# Motor_Driver.net
KiCad netlist of a schematic drawn in Altium Designer
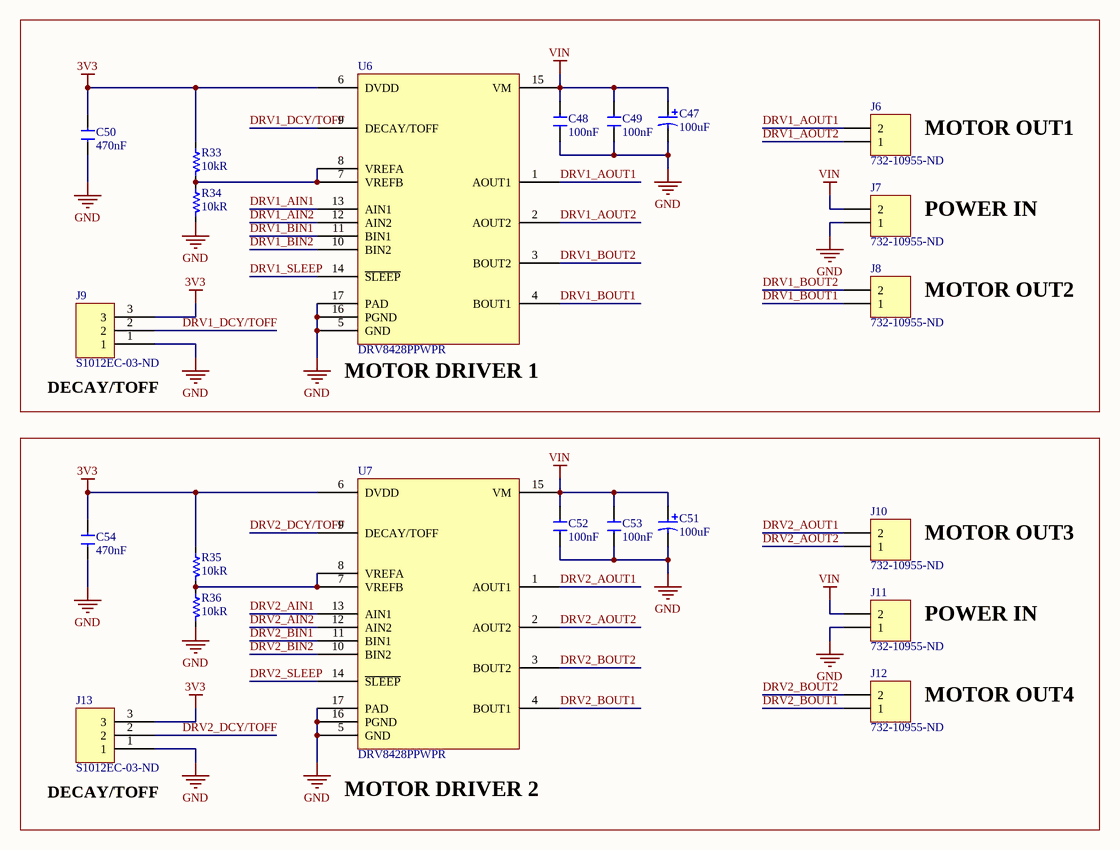
[diagram p0: Motor Driver.SchDoc]

(export (version "E")
  (design (tool "Eeschema 10.0.6"))
  (components
    (comp (ref "C47")
      (value "CAP_100uF_%20_25V_ALUM_SMD")
      (footprint "RADIAL-2_6.3MMX7.7MM")
      (description "CAP.EL.100uF 25V 6.3x7.7 105C 5000HRS SMD")
      (fields
        (field (name "TOLERANCE") "20%")
        (field (name "MANUFACTURER") "SAMYOUNG")
        (field (name "CAPACITANCE") "100uF")
      )
      (libsource (lib "Main Schematic Library") (part "CAP_100uF_%20_25V_ALUM_SMD"))
    )
    (comp (ref "C48")
      (value "CAP_0.1uF_50V_0805_X7R_CER")
      (footprint "0805_CAP")
      (description "Cap Ceramic 0.1uF 50V X7R 20% SMD 0805 125C Paper T/R")
      (fields
        (field (name "MANUFACTURER") "KEMET")
        (field (name "MANUFACTURER PART NUMBER") "C0805C104M5RACTU")
        (field (name "CAPACITANCE") "100nF")
      )
      (libsource (lib "Main Component Library") (part "CAP_0.1uF_50V_0805_X7R_CER"))
    )
    (comp (ref "C49")
      (value "CAP_0.1uF_50V_0805_X7R_CER")
      (footprint "0805_CAP")
      (description "Cap Ceramic 0.1uF 50V X7R 20% SMD 0805 125C Paper T/R")
      (fields
        (field (name "MANUFACTURER") "KEMET")
        (field (name "MANUFACTURER PART NUMBER") "C0805C104M5RACTU")
        (field (name "CAPACITANCE") "100nF")
      )
      (libsource (lib "Main Component Library") (part "CAP_0.1uF_50V_0805_X7R_CER"))
    )
    (comp (ref "C50")
      (value "CAP_0.47uF_%10_0805_25V_X7R_CER")
      (footprint "0805_CAP")
      (description "Cap Ceramic 0.47uF 25V X7R 10% SMD 0805 125°C Embossed Plastic T/R")
      (fields
        (field (name "MANUFACTURER") "Samsung")
        (field (name "MANUFACTURER PART NUMBER") "CL21B474KAFNNNG")
        (field (name "CAPACITANCE") "470nF")
      )
      (libsource (lib "Main Component Library") (part "CAP_0.47uF_%10_0805_25V_X7R_CER"))
    )
    (comp (ref "C51")
      (value "CAP_100uF_%20_25V_ALUM_SMD")
      (footprint "RADIAL-2_6.3MMX7.7MM")
      (description "CAP.EL.100uF 25V 6.3x7.7 105C 5000HRS SMD")
      (fields
        (field (name "TOLERANCE") "20%")
        (field (name "MANUFACTURER") "SAMYOUNG")
        (field (name "CAPACITANCE") "100uF")
      )
      (libsource (lib "Main Schematic Library") (part "CAP_100uF_%20_25V_ALUM_SMD"))
    )
    (comp (ref "C52")
      (value "CAP_0.1uF_50V_0805_X7R_CER")
      (footprint "0805_CAP")
      (description "Cap Ceramic 0.1uF 50V X7R 20% SMD 0805 125C Paper T/R")
      (fields
        (field (name "MANUFACTURER") "KEMET")
        (field (name "MANUFACTURER PART NUMBER") "C0805C104M5RACTU")
        (field (name "CAPACITANCE") "100nF")
      )
      (libsource (lib "Main Component Library") (part "CAP_0.1uF_50V_0805_X7R_CER"))
    )
    (comp (ref "C53")
      (value "CAP_0.1uF_50V_0805_X7R_CER")
      (footprint "0805_CAP")
      (description "Cap Ceramic 0.1uF 50V X7R 20% SMD 0805 125C Paper T/R")
      (fields
        (field (name "MANUFACTURER") "KEMET")
        (field (name "MANUFACTURER PART NUMBER") "C0805C104M5RACTU")
        (field (name "CAPACITANCE") "100nF")
      )
      (libsource (lib "Main Component Library") (part "CAP_0.1uF_50V_0805_X7R_CER"))
    )
    (comp (ref "C54")
      (value "CAP_0.47uF_%10_0805_25V_X7R_CER")
      (footprint "0805_CAP")
      (description "Cap Ceramic 0.47uF 25V X7R 10% SMD 0805 125°C Embossed Plastic T/R")
      (fields
        (field (name "MANUFACTURER") "Samsung")
        (field (name "MANUFACTURER PART NUMBER") "CL21B474KAFNNNG")
        (field (name "CAPACITANCE") "470nF")
      )
      (libsource (lib "Main Component Library") (part "CAP_0.47uF_%10_0805_25V_X7R_CER"))
    )
    (comp (ref "J6")
      (value "CONN_1X2_Terminal Block")
      (footprint "1x2_TERMINAL BLOCK")
      (description "Series 1377 - 5.00 mm Horizontal Entry with Pressure Clamp WR-TBL, 2 pin")
      (fields
        (field (name "MANUFACTURER") "Wurth Electronics")
        (field (name "MANUFACTURER PART NUMBER") "691137710002")
        (field (name "SUPPLIER PART NUMBER 1") "732-10955-ND")
      )
      (libsource (lib "Main Component Library") (part "CONN_1X2_Terminal Block"))
    )
    (comp (ref "J7")
      (value "CONN_1X2_Terminal Block")
      (footprint "1x2_TERMINAL BLOCK")
      (description "Series 1377 - 5.00 mm Horizontal Entry with Pressure Clamp WR-TBL, 2 pin")
      (fields
        (field (name "MANUFACTURER") "Wurth Electronics")
        (field (name "MANUFACTURER PART NUMBER") "691137710002")
        (field (name "SUPPLIER PART NUMBER 1") "732-10955-ND")
      )
      (libsource (lib "Main Component Library") (part "CONN_1X2_Terminal Block"))
    )
    (comp (ref "J8")
      (value "CONN_1X2_Terminal Block")
      (footprint "1x2_TERMINAL BLOCK")
      (description "Series 1377 - 5.00 mm Horizontal Entry with Pressure Clamp WR-TBL, 2 pin")
      (fields
        (field (name "MANUFACTURER") "Wurth Electronics")
        (field (name "MANUFACTURER PART NUMBER") "691137710002")
        (field (name "SUPPLIER PART NUMBER 1") "732-10955-ND")
      )
      (libsource (lib "Main Component Library") (part "CONN_1X2_Terminal Block"))
    )
    (comp (ref "J9")
      (value "CONN_1X3_2.54mm_Male Header")
      (footprint "DIP_1X3_MALE_HEADER_2.54_PITCH")
      (description "Conn Header Vert 3POS 2.54MM")
      (fields
        (field (name "MANUFACTURER") "Sullins")
        (field (name "MANUFACTURER PART NUMBER") "PREC003SAAN-RC")
        (field (name "SUPPLIER PART NUMBER 1") "S1012EC-03-ND")
      )
      (libsource (lib "Main Schematic Library") (part "CONN_1X3_2.54mm_Male Header"))
    )
    (comp (ref "J10")
      (value "CONN_1X2_Terminal Block")
      (footprint "1x2_TERMINAL BLOCK")
      (description "Series 1377 - 5.00 mm Horizontal Entry with Pressure Clamp WR-TBL, 2 pin")
      (fields
        (field (name "MANUFACTURER") "Wurth Electronics")
        (field (name "MANUFACTURER PART NUMBER") "691137710002")
        (field (name "SUPPLIER PART NUMBER 1") "732-10955-ND")
      )
      (libsource (lib "Main Component Library") (part "CONN_1X2_Terminal Block"))
    )
    (comp (ref "J11")
      (value "CONN_1X2_Terminal Block")
      (footprint "1x2_TERMINAL BLOCK")
      (description "Series 1377 - 5.00 mm Horizontal Entry with Pressure Clamp WR-TBL, 2 pin")
      (fields
        (field (name "MANUFACTURER") "Wurth Electronics")
        (field (name "MANUFACTURER PART NUMBER") "691137710002")
        (field (name "SUPPLIER PART NUMBER 1") "732-10955-ND")
      )
      (libsource (lib "Main Component Library") (part "CONN_1X2_Terminal Block"))
    )
    (comp (ref "J12")
      (value "CONN_1X2_Terminal Block")
      (footprint "1x2_TERMINAL BLOCK")
      (description "Series 1377 - 5.00 mm Horizontal Entry with Pressure Clamp WR-TBL, 2 pin")
      (fields
        (field (name "MANUFACTURER") "Wurth Electronics")
        (field (name "MANUFACTURER PART NUMBER") "691137710002")
        (field (name "SUPPLIER PART NUMBER 1") "732-10955-ND")
      )
      (libsource (lib "Main Component Library") (part "CONN_1X2_Terminal Block"))
    )
    (comp (ref "J13")
      (value "CONN_1X3_2.54mm_Male Header")
      (footprint "DIP_1X3_MALE_HEADER_2.54_PITCH")
      (description "Conn Header Vert 3POS 2.54MM")
      (fields
        (field (name "MANUFACTURER") "Sullins")
        (field (name "MANUFACTURER PART NUMBER") "PREC003SAAN-RC")
        (field (name "SUPPLIER PART NUMBER 1") "S1012EC-03-ND")
      )
      (libsource (lib "Main Schematic Library") (part "CONN_1X3_2.54mm_Male Header"))
    )
    (comp (ref "R33")
      (value "10k Ohms")
      (footprint "0805_RES")
      (description "Res SMD 0805 10K 1% 0.125W T.C.100PPM")
      (fields
        (field (name "MANUFACTURER") "TDK")
        (field (name "MANUFACTURER PART NUMBER") "C2012X7R1H104K085AA")
        (field (name "RESISTANCE") "10kR")
      )
      (libsource (lib "Main Component Library") (part "RES_10K OHM_%1_0805_1/8W"))
    )
    (comp (ref "R34")
      (value "10k Ohms")
      (footprint "0805_RES")
      (description "Res SMD 0805 10K 1% 0.125W T.C.100PPM")
      (fields
        (field (name "MANUFACTURER") "TDK")
        (field (name "MANUFACTURER PART NUMBER") "C2012X7R1H104K085AA")
        (field (name "RESISTANCE") "10kR")
      )
      (libsource (lib "Main Component Library") (part "RES_10K OHM_%1_0805_1/8W"))
    )
    (comp (ref "R35")
      (value "10k Ohms")
      (footprint "0805_RES")
      (description "Res SMD 0805 10K 1% 0.125W T.C.100PPM")
      (fields
        (field (name "MANUFACTURER") "TDK")
        (field (name "MANUFACTURER PART NUMBER") "C2012X7R1H104K085AA")
        (field (name "RESISTANCE") "10kR")
      )
      (libsource (lib "Main Component Library") (part "RES_10K OHM_%1_0805_1/8W"))
    )
    (comp (ref "R36")
      (value "10k Ohms")
      (footprint "0805_RES")
      (description "Res SMD 0805 10K 1% 0.125W T.C.100PPM")
      (fields
        (field (name "MANUFACTURER") "TDK")
        (field (name "MANUFACTURER PART NUMBER") "C2012X7R1H104K085AA")
        (field (name "RESISTANCE") "10kR")
      )
      (libsource (lib "Main Component Library") (part "RES_10K OHM_%1_0805_1/8W"))
    )
    (comp (ref "U6")
      (value "DRV8428PPWPR")
      (footprint "TSOP65P640X120_HS-17N")
      (fields (field (name "MANUFACTURER") "Texas Instruments"))
      (libsource (lib "Main Schematic Library") (part "IC_MOTOR DRIVER_DRV8428PPWPR"))
    )
    (comp (ref "U7")
      (value "DRV8428PPWPR")
      (footprint "TSOP65P640X120_HS-17N")
      (fields (field (name "MANUFACTURER") "Texas Instruments"))
      (libsource (lib "Main Schematic Library") (part "IC_MOTOR DRIVER_DRV8428PPWPR"))
    )
  )
  (nets
    (net (code "1") (name "/DRV1_AIN1") (class "Default")
      (node (ref "U6") (pin "13") (pinfunction "AIN1_13") (pintype "passive"))
    )
    (net (code "2") (name "/DRV1_AIN2") (class "Default")
      (node (ref "U6") (pin "12") (pinfunction "AIN2_12") (pintype "passive"))
    )
    (net (code "3") (name "/DRV1_AOUT1") (class "Default")
      (node (ref "J6") (pin "2") (pinfunction "2_2") (pintype "passive"))
      (node (ref "U6") (pin "1") (pinfunction "AOUT1_1") (pintype "passive"))
    )
    (net (code "4") (name "/DRV1_AOUT2") (class "Default")
      (node (ref "J6") (pin "1") (pinfunction "1_1") (pintype "passive"))
      (node (ref "U6") (pin "2") (pinfunction "AOUT2_2") (pintype "passive"))
    )
    (net (code "5") (name "/DRV1_BIN1") (class "Default")
      (node (ref "U6") (pin "11") (pinfunction "BIN1_11") (pintype "passive"))
    )
    (net (code "6") (name "/DRV1_BIN2") (class "Default")
      (node (ref "U6") (pin "10") (pinfunction "BIN2_10") (pintype "passive"))
    )
    (net (code "7") (name "/DRV1_BOUT1") (class "Default")
      (node (ref "J8") (pin "1") (pinfunction "1_1") (pintype "passive"))
      (node (ref "U6") (pin "4") (pinfunction "BOUT1_4") (pintype "passive"))
    )
    (net (code "8") (name "/DRV1_BOUT2") (class "Default")
      (node (ref "J8") (pin "2") (pinfunction "2_2") (pintype "passive"))
      (node (ref "U6") (pin "3") (pinfunction "BOUT2_3") (pintype "passive"))
    )
    (net (code "9") (name "/DRV1_DCY{slash}TOFF") (class "Default")
      (node (ref "J9") (pin "2") (pinfunction "2_2") (pintype "passive"))
      (node (ref "U6") (pin "9") (pinfunction "DECAY/TOFF_9") (pintype "passive"))
    )
    (net (code "10") (name "/DRV1_SLEEP") (class "Default")
      (node (ref "U6") (pin "14") (pinfunction "~{SLEEP}_14") (pintype "passive"))
    )
    (net (code "11") (name "/DRV2_AIN1") (class "Default")
      (node (ref "U7") (pin "13") (pinfunction "AIN1_13") (pintype "passive"))
    )
    (net (code "12") (name "/DRV2_AIN2") (class "Default")
      (node (ref "U7") (pin "12") (pinfunction "AIN2_12") (pintype "passive"))
    )
    (net (code "13") (name "/DRV2_AOUT1") (class "Default")
      (node (ref "J10") (pin "2") (pinfunction "2_2") (pintype "passive"))
      (node (ref "U7") (pin "1") (pinfunction "AOUT1_1") (pintype "passive"))
    )
    (net (code "14") (name "/DRV2_AOUT2") (class "Default")
      (node (ref "J10") (pin "1") (pinfunction "1_1") (pintype "passive"))
      (node (ref "U7") (pin "2") (pinfunction "AOUT2_2") (pintype "passive"))
    )
    (net (code "15") (name "/DRV2_BIN1") (class "Default")
      (node (ref "U7") (pin "11") (pinfunction "BIN1_11") (pintype "passive"))
    )
    (net (code "16") (name "/DRV2_BIN2") (class "Default")
      (node (ref "U7") (pin "10") (pinfunction "BIN2_10") (pintype "passive"))
    )
    (net (code "17") (name "/DRV2_BOUT1") (class "Default")
      (node (ref "J12") (pin "1") (pinfunction "1_1") (pintype "passive"))
      (node (ref "U7") (pin "4") (pinfunction "BOUT1_4") (pintype "passive"))
    )
    (net (code "18") (name "/DRV2_BOUT2") (class "Default")
      (node (ref "J12") (pin "2") (pinfunction "2_2") (pintype "passive"))
      (node (ref "U7") (pin "3") (pinfunction "BOUT2_3") (pintype "passive"))
    )
    (net (code "19") (name "/DRV2_DCY{slash}TOFF") (class "Default")
      (node (ref "J13") (pin "2") (pinfunction "2_2") (pintype "passive"))
      (node (ref "U7") (pin "9") (pinfunction "DECAY/TOFF_9") (pintype "passive"))
    )
    (net (code "20") (name "/DRV2_SLEEP") (class "Default")
      (node (ref "U7") (pin "14") (pinfunction "~{SLEEP}_14") (pintype "passive"))
    )
    (net (code "21") (name "3V3") (class "Default")
      (node (ref "C50") (pin "2") (pinfunction "2_2") (pintype "passive"))
      (node (ref "C54") (pin "2") (pinfunction "2_2") (pintype "passive"))
      (node (ref "J13") (pin "3") (pinfunction "3_3") (pintype "passive"))
      (node (ref "J9") (pin "3") (pinfunction "3_3") (pintype "passive"))
      (node (ref "R33") (pin "2") (pinfunction "2_2") (pintype "passive"))
      (node (ref "R35") (pin "2") (pinfunction "2_2") (pintype "passive"))
      (node (ref "U6") (pin "6") (pinfunction "DVDD_6") (pintype "passive"))
      (node (ref "U7") (pin "6") (pinfunction "DVDD_6") (pintype "passive"))
    )
    (net (code "22") (name "GND") (class "Default")
      (node (ref "C47") (pin "2") (pinfunction "2_2") (pintype "passive"))
      (node (ref "C48") (pin "1") (pinfunction "1_1") (pintype "passive"))
      (node (ref "C49") (pin "1") (pinfunction "1_1") (pintype "passive"))
      (node (ref "C50") (pin "1") (pinfunction "1_1") (pintype "passive"))
      (node (ref "C51") (pin "2") (pinfunction "2_2") (pintype "passive"))
      (node (ref "C52") (pin "1") (pinfunction "1_1") (pintype "passive"))
      (node (ref "C53") (pin "1") (pinfunction "1_1") (pintype "passive"))
      (node (ref "C54") (pin "1") (pinfunction "1_1") (pintype "passive"))
      (node (ref "J11") (pin "1") (pinfunction "1_1") (pintype "passive"))
      (node (ref "J13") (pin "1") (pinfunction "1_1") (pintype "passive"))
      (node (ref "J7") (pin "1") (pinfunction "1_1") (pintype "passive"))
      (node (ref "J9") (pin "1") (pinfunction "1_1") (pintype "passive"))
      (node (ref "R34") (pin "1") (pinfunction "1_1") (pintype "passive"))
      (node (ref "R36") (pin "1") (pinfunction "1_1") (pintype "passive"))
      (node (ref "U6") (pin "16") (pinfunction "PGND_16") (pintype "passive"))
      (node (ref "U6") (pin "17") (pinfunction "PAD_17") (pintype "passive"))
      (node (ref "U6") (pin "5") (pinfunction "GND_5") (pintype "passive"))
      (node (ref "U7") (pin "16") (pinfunction "PGND_16") (pintype "passive"))
      (node (ref "U7") (pin "17") (pinfunction "PAD_17") (pintype "passive"))
      (node (ref "U7") (pin "5") (pinfunction "GND_5") (pintype "passive"))
    )
    (net (code "23") (name "Net-(U6-VREFA)") (class "Default")
      (node (ref "R33") (pin "1") (pinfunction "1_1") (pintype "passive"))
      (node (ref "R34") (pin "2") (pinfunction "2_2") (pintype "passive"))
      (node (ref "U6") (pin "7") (pinfunction "VREFB_7") (pintype "passive"))
      (node (ref "U6") (pin "8") (pinfunction "VREFA_8") (pintype "passive"))
    )
    (net (code "24") (name "Net-(U7-VREFA)") (class "Default")
      (node (ref "R35") (pin "1") (pinfunction "1_1") (pintype "passive"))
      (node (ref "R36") (pin "2") (pinfunction "2_2") (pintype "passive"))
      (node (ref "U7") (pin "7") (pinfunction "VREFB_7") (pintype "passive"))
      (node (ref "U7") (pin "8") (pinfunction "VREFA_8") (pintype "passive"))
    )
    (net (code "25") (name "VIN") (class "Default")
      (node (ref "C47") (pin "1") (pinfunction "1_1") (pintype "passive"))
      (node (ref "C48") (pin "2") (pinfunction "2_2") (pintype "passive"))
      (node (ref "C49") (pin "2") (pinfunction "2_2") (pintype "passive"))
      (node (ref "C51") (pin "1") (pinfunction "1_1") (pintype "passive"))
      (node (ref "C52") (pin "2") (pinfunction "2_2") (pintype "passive"))
      (node (ref "C53") (pin "2") (pinfunction "2_2") (pintype "passive"))
      (node (ref "J11") (pin "2") (pinfunction "2_2") (pintype "passive"))
      (node (ref "J7") (pin "2") (pinfunction "2_2") (pintype "passive"))
      (node (ref "U6") (pin "15") (pinfunction "VM_15") (pintype "passive"))
      (node (ref "U7") (pin "15") (pinfunction "VM_15") (pintype "passive"))
    )
  )
)
